# Power_Managemend_and_Connectors.net
KiCad netlist of a schematic drawn in Altium Designer
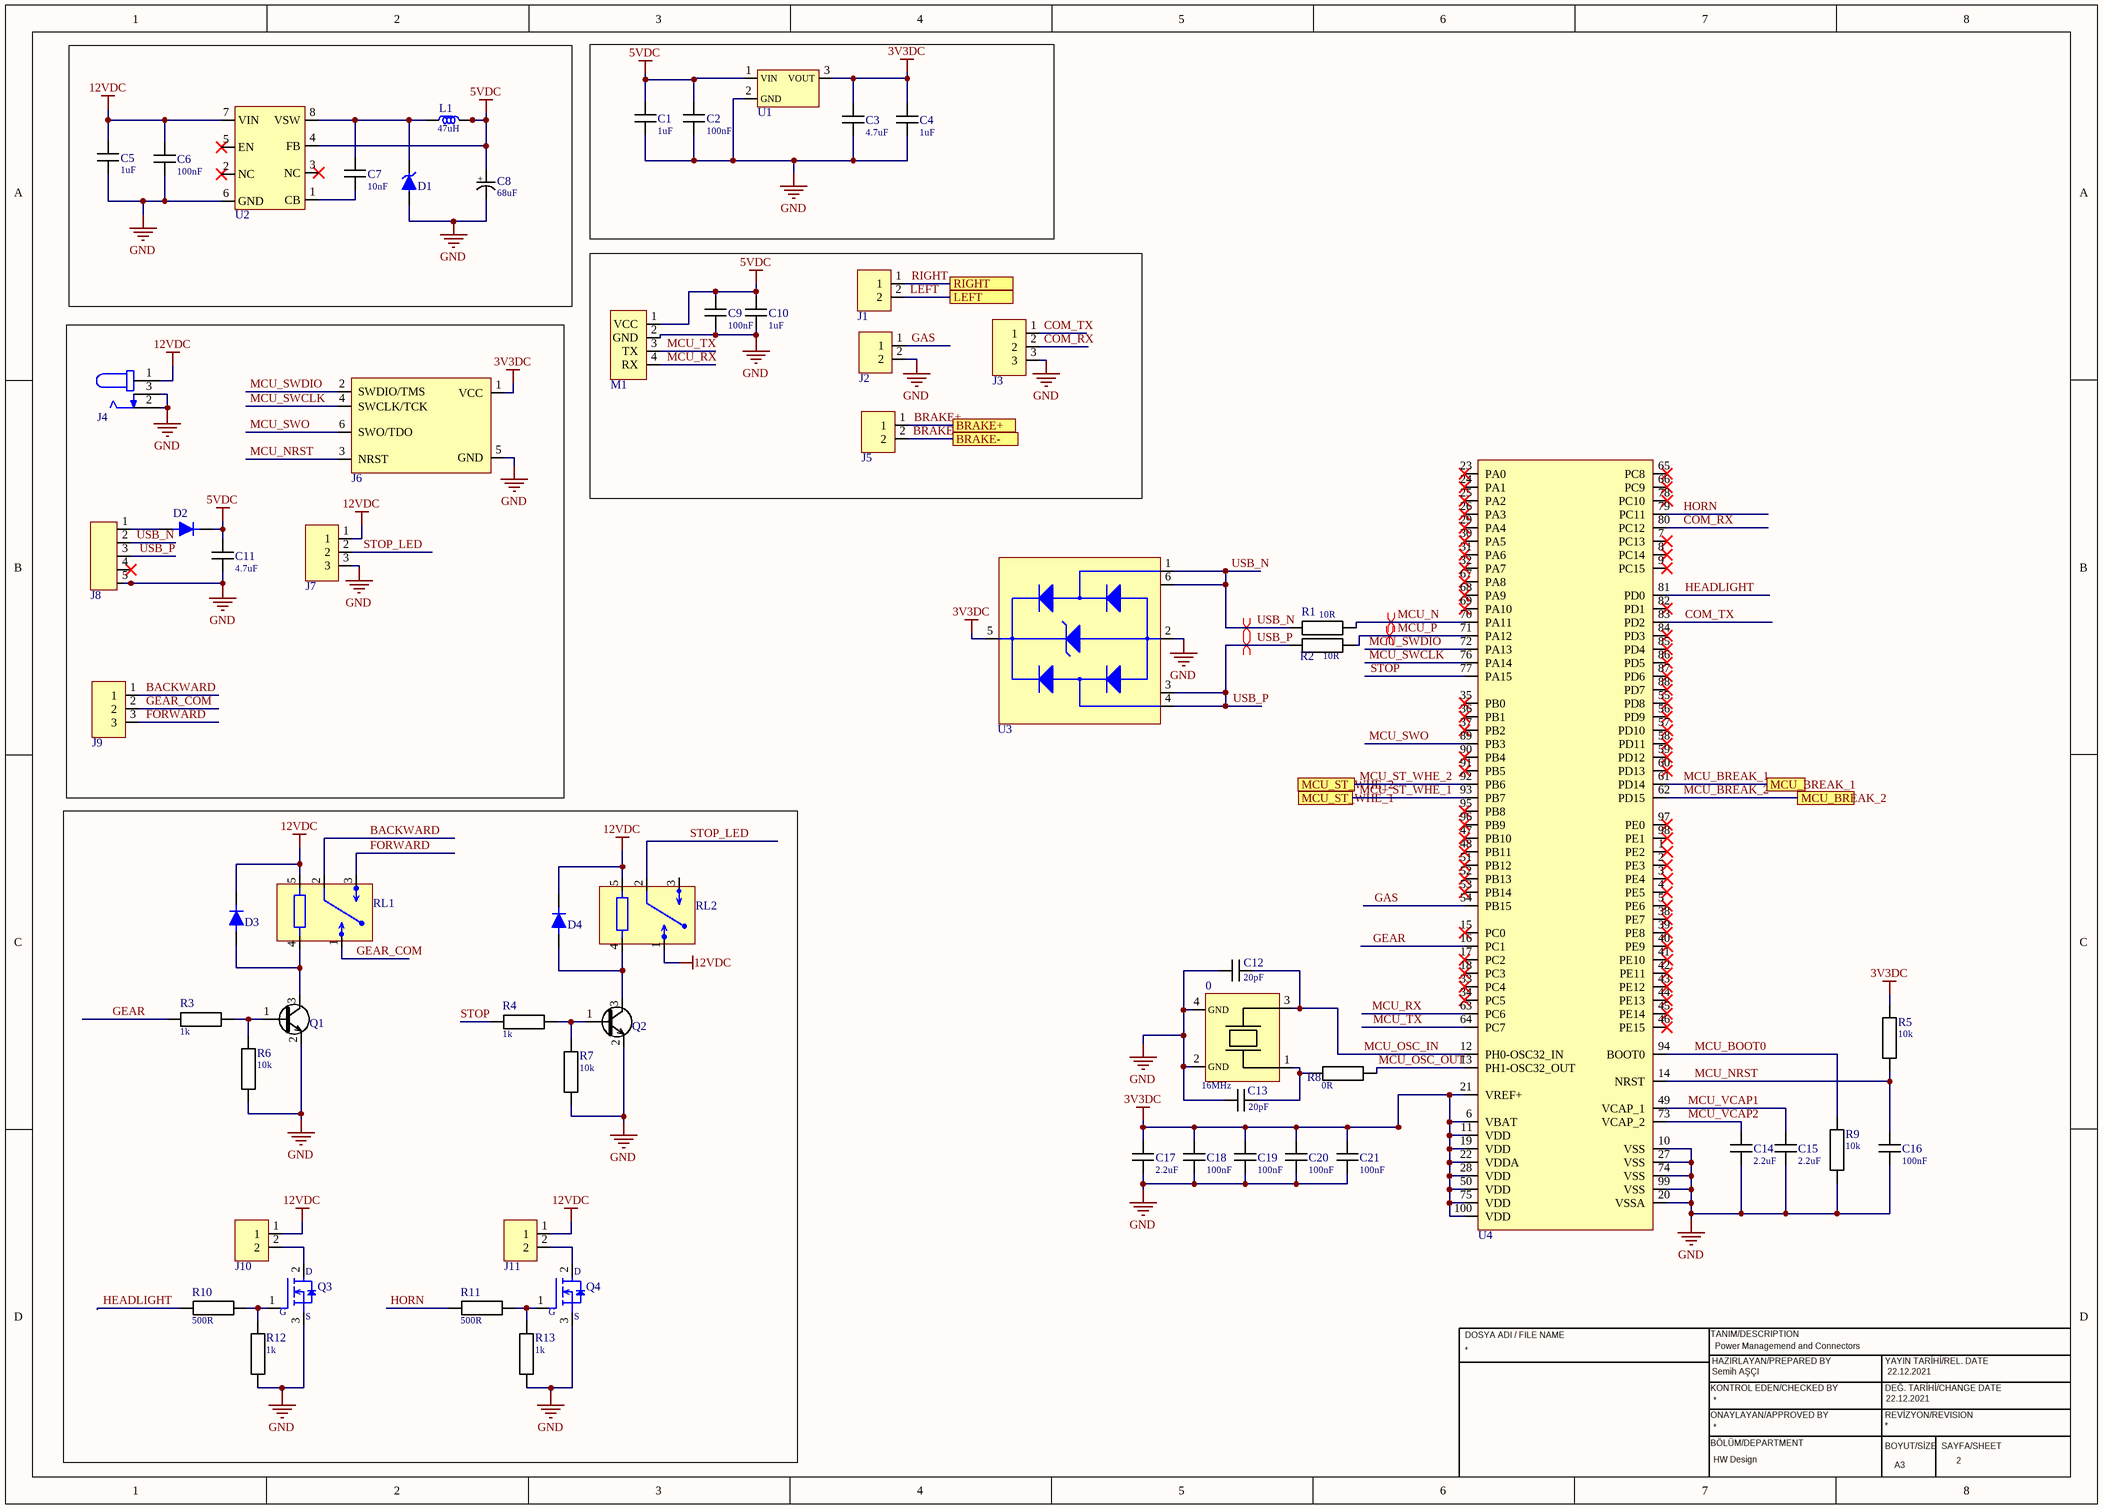
[diagram p0: Power Managemend and Connectors.SchDoc]

(export (version "E")
  (design (tool "Eeschema 10.0.6"))
  (components
    (comp (ref "0")
      (value "ECS-160-20-30B-TR")
      (footprint "ECS")
      (description "Crystal 16MHz ±30ppm (Tol) ±50ppm (Stability) 20pF FUND 50Ohm 4-Pin Mini-SMD T/R")
      (fields
        (field (name "MANUFACTURER") "ECS International")
        (field (name "TOLERANCE") "50ppm")
        (field (name "FREQUENCY") "16MHz")
        (field (name "DESIGNED BY") "Semih AŞÇI")
      )
      (libsource (lib "Integrated_Library1") (part "CRYSTAL 16 MHZ"))
    )
    (comp (ref "C1")
      (value "C0805C105M5RACTU")
      (footprint "CAP_0805")
      (description "Cap Ceramic 1uF %20 SMD 0805")
      (fields
        (field (name "MANUFACTURER") "KEMET")
        (field (name "TOLERANCE") "20%")
        (field (name "CAPACITANCE") "1uF")
        (field (name "DESIGNED BY") "Semih AŞÇI")
      )
      (libsource (lib "Integrated_Library1") (part "CAP 1uF 0805"))
    )
    (comp (ref "C2")
      (value "C0805C104K5RAC7800")
      (footprint "CAP_0805")
      (description "Cap Ceramic 100nF %10 SMD 0805")
      (fields
        (field (name "MANUFACTURER") "KEMET")
        (field (name "MANUFACTURER PART NUMBER") "C0805C104K5RACTU")
        (field (name "CAPACITANCE") "100nF")
        (field (name "DESIGNED BY") "Semih AŞÇI")
      )
      (libsource (lib "Integrated_Library1") (part "CAP 100nF 0805"))
    )
    (comp (ref "C3")
      (value "CL21A475KAQNNNE")
      (footprint "CAP_0805")
      (description "Cap Ceramic 4.7uF 25V X5R 10% SMD 0805 85C Embossed T/R")
      (fields
        (field (name "MANUFACTURER") "Samsung")
        (field (name "TOLERANCE") "10%")
        (field (name "CAPACITANCE") "4.7uF")
        (field (name "DESIGNED BY") "Semih AŞÇI")
      )
      (libsource (lib "Integrated_Library1") (part "CAP 4,7uF 0805"))
    )
    (comp (ref "C4")
      (value "C0805C105M5RACTU")
      (footprint "CAP_0805")
      (description "Cap Ceramic 1uF %20 SMD 0805")
      (fields
        (field (name "MANUFACTURER") "KEMET")
        (field (name "TOLERANCE") "20%")
        (field (name "CAPACITANCE") "1uF")
        (field (name "DESIGNED BY") "Semih AŞÇI")
      )
      (libsource (lib "Integrated_Library1") (part "CAP 1uF 0805"))
    )
    (comp (ref "C5")
      (value "C0805C105M5RACTU")
      (footprint "CAP_0805")
      (description "Cap Ceramic 1uF %20 SMD 0805")
      (fields
        (field (name "MANUFACTURER") "KEMET")
        (field (name "TOLERANCE") "20%")
        (field (name "CAPACITANCE") "1uF")
        (field (name "DESIGNED BY") "Semih AŞÇI")
      )
      (libsource (lib "Integrated_Library1") (part "CAP 1uF 0805"))
    )
    (comp (ref "C6")
      (value "C0805C104K5RAC7800")
      (footprint "CAP_0805")
      (description "Cap Ceramic 100nF %10 SMD 0805")
      (fields
        (field (name "MANUFACTURER") "KEMET")
        (field (name "MANUFACTURER PART NUMBER") "C0805C104K5RACTU")
        (field (name "CAPACITANCE") "100nF")
        (field (name "DESIGNED BY") "Semih AŞÇI")
      )
      (libsource (lib "Integrated_Library1") (part "CAP 100nF 0805"))
    )
    (comp (ref "C7")
      (value "0603B103K160CT")
      (footprint "CAP_0603")
      (description "Cap Ceramic 10nF %10 SMD 0603")
      (fields
        (field (name "MANUFACTURER") "Walsin Technologies")
        (field (name "TOLERANCE") "10%")
        (field (name "CAPACITANCE") "10nF")
        (field (name "DESIGNED BY") "Semih AŞÇI")
      )
      (libsource (lib "Integrated_Library1") (part "CAP 10nF 0603"))
    )
    (comp (ref "C8")
      (value "EEV686M035A9HAA")
      (footprint "CAP_ELEC_EEE-HA0J101WR")
      (description "Cap Aluminum Lytic 68uF 35V 20% (6.3 X 7.7mm) SMD 280mA 2000h 105C T/R")
      (fields
        (field (name "MANUFACTURER") "KEMET")
        (field (name "TOLERANCE") "20%")
        (field (name "CAPACITANCE") "68uF")
        (field (name "DESIGNED BY") "Semih AŞÇI")
      )
      (libsource (lib "Integrated_Library1") (part "CAP 68uF Polar SMD"))
    )
    (comp (ref "C9")
      (value "C0805C104K5RAC7800")
      (footprint "CAP_0805")
      (description "Cap Ceramic 100nF %10 SMD 0805")
      (fields
        (field (name "MANUFACTURER") "KEMET")
        (field (name "MANUFACTURER PART NUMBER") "C0805C104K5RACTU")
        (field (name "CAPACITANCE") "100nF")
        (field (name "DESIGNED BY") "Semih AŞÇI")
      )
      (libsource (lib "Integrated_Library1") (part "CAP 100nF 0805"))
    )
    (comp (ref "C10")
      (value "C0805C105M5RACTU")
      (footprint "CAP_0805")
      (description "Cap Ceramic 1uF %20 SMD 0805")
      (fields
        (field (name "MANUFACTURER") "KEMET")
        (field (name "TOLERANCE") "20%")
        (field (name "CAPACITANCE") "1uF")
        (field (name "DESIGNED BY") "Semih AŞÇI")
      )
      (libsource (lib "Integrated_Library1") (part "CAP 1uF 0805"))
    )
    (comp (ref "C11")
      (value "CL21A475KAQNNNE")
      (footprint "CAP_0805")
      (description "Cap Ceramic 4.7uF 25V X5R 10% SMD 0805 85C Embossed T/R")
      (fields
        (field (name "MANUFACTURER") "Samsung")
        (field (name "TOLERANCE") "10%")
        (field (name "CAPACITANCE") "4.7uF")
        (field (name "DESIGNED BY") "Semih AŞÇI")
      )
      (libsource (lib "Integrated_Library1") (part "CAP 4,7uF 0805"))
    )
    (comp (ref "C12")
      (value "C0603C200F5GAC7867")
      (footprint "CAP_0603")
      (description "Cap Ceramic 20pF SMD 0603")
      (fields
        (field (name "MANUFACTURER") "KEMET")
        (field (name "CAPACITANCE") "20pF")
        (field (name "DESIGNED BY") "Semih AŞÇI")
      )
      (libsource (lib "Integrated_Library1") (part "CAP 20pF 0603"))
    )
    (comp (ref "C13")
      (value "C0603C200F5GAC7867")
      (footprint "CAP_0603")
      (description "Cap Ceramic 20pF SMD 0603")
      (fields
        (field (name "MANUFACTURER") "KEMET")
        (field (name "CAPACITANCE") "20pF")
        (field (name "DESIGNED BY") "Semih AŞÇI")
      )
      (libsource (lib "Integrated_Library1") (part "CAP 20pF 0603"))
    )
    (comp (ref "C14")
      (value "C1206C225K5RACAUTO")
      (footprint "CAP_1206")
      (description "Cap Ceramic 2.2uF %10 SMD 1206")
      (fields
        (field (name "MANUFACTURER") "KEMET")
        (field (name "TOLERANCE") "10%")
        (field (name "CAPACITANCE") "2.2uF")
        (field (name "DESIGNED BY") "Semih AŞÇI")
      )
      (libsource (lib "Integrated_Library1") (part "CAP 2.2uF 1206"))
    )
    (comp (ref "C15")
      (value "C1206C225K5RACAUTO")
      (footprint "CAP_1206")
      (description "Cap Ceramic 2.2uF %10 SMD 1206")
      (fields
        (field (name "MANUFACTURER") "KEMET")
        (field (name "TOLERANCE") "10%")
        (field (name "CAPACITANCE") "2.2uF")
        (field (name "DESIGNED BY") "Semih AŞÇI")
      )
      (libsource (lib "Integrated_Library1") (part "CAP 2.2uF 1206"))
    )
    (comp (ref "C16")
      (value "C0805C104K5RAC7800")
      (footprint "CAP_0805")
      (description "Cap Ceramic 100nF %10 SMD 0805")
      (fields
        (field (name "MANUFACTURER") "KEMET")
        (field (name "MANUFACTURER PART NUMBER") "C0805C104K5RACTU")
        (field (name "CAPACITANCE") "100nF")
        (field (name "DESIGNED BY") "Semih AŞÇI")
      )
      (libsource (lib "Integrated_Library1") (part "CAP 100nF 0805"))
    )
    (comp (ref "C17")
      (value "C1206C225K5RACAUTO")
      (footprint "CAP_1206")
      (description "Cap Ceramic 2.2uF %10 SMD 1206")
      (fields
        (field (name "MANUFACTURER") "KEMET")
        (field (name "TOLERANCE") "10%")
        (field (name "CAPACITANCE") "2.2uF")
        (field (name "DESIGNED BY") "Semih AŞÇI")
      )
      (libsource (lib "Integrated_Library1") (part "CAP 2.2uF 1206"))
    )
    (comp (ref "C18")
      (value "C0805C104K5RAC7800")
      (footprint "CAP_0805")
      (description "Cap Ceramic 100nF %10 SMD 0805")
      (fields
        (field (name "MANUFACTURER") "KEMET")
        (field (name "MANUFACTURER PART NUMBER") "C0805C104K5RACTU")
        (field (name "CAPACITANCE") "100nF")
        (field (name "DESIGNED BY") "Semih AŞÇI")
      )
      (libsource (lib "Integrated_Library1") (part "CAP 100nF 0805"))
    )
    (comp (ref "C19")
      (value "C0805C104K5RAC7800")
      (footprint "CAP_0805")
      (description "Cap Ceramic 100nF %10 SMD 0805")
      (fields
        (field (name "MANUFACTURER") "KEMET")
        (field (name "MANUFACTURER PART NUMBER") "C0805C104K5RACTU")
        (field (name "CAPACITANCE") "100nF")
        (field (name "DESIGNED BY") "Semih AŞÇI")
      )
      (libsource (lib "Integrated_Library1") (part "CAP 100nF 0805"))
    )
    (comp (ref "C20")
      (value "C0805C104K5RAC7800")
      (footprint "CAP_0805")
      (description "Cap Ceramic 100nF %10 SMD 0805")
      (fields
        (field (name "MANUFACTURER") "KEMET")
        (field (name "MANUFACTURER PART NUMBER") "C0805C104K5RACTU")
        (field (name "CAPACITANCE") "100nF")
        (field (name "DESIGNED BY") "Semih AŞÇI")
      )
      (libsource (lib "Integrated_Library1") (part "CAP 100nF 0805"))
    )
    (comp (ref "C21")
      (value "C0805C104K5RAC7800")
      (footprint "CAP_0805")
      (description "Cap Ceramic 100nF %10 SMD 0805")
      (fields
        (field (name "MANUFACTURER") "KEMET")
        (field (name "MANUFACTURER PART NUMBER") "C0805C104K5RACTU")
        (field (name "CAPACITANCE") "100nF")
        (field (name "DESIGNED BY") "Semih AŞÇI")
      )
      (libsource (lib "Integrated_Library1") (part "CAP 100nF 0805"))
    )
    (comp (ref "D1")
      (value "1SMB5919BT3G")
      (footprint "SMB")
      (description "Diode, Zener, Vr 5.6V, If 200mA, Pkg SMB, Vf 1.5V, Tj +150degc, Pd 3W, Ir 66.9mA")
      (fields
        (field (name "MANUFACTURER") "ON Semiconductor")
        (field (name "TOLERANCE") "5%")
        (field (name "DESIGNED BY") "Semih AŞÇI")
      )
      (libsource (lib "Integrated_Library1") (part "1SMB5919BT3G"))
    )
    (comp (ref "D2")
      (value "1N4148WS")
      (footprint "SOD323F")
      (description "Diode Small Signal Switching 100V 0.15A Automotive 2-Pin SOD-323F T/R")
      (fields
        (field (name "MANUFACTURER") "ON Semiconductor / Fairchild")
        (field (name "DESIGNED BY") "Semih AŞÇI")
      )
      (libsource (lib "Integrated_Library1") (part "1N4148SW"))
    )
    (comp (ref "D3")
      (value "1N4148WS")
      (footprint "SOD323F")
      (description "Diode Small Signal Switching 100V 0.15A Automotive 2-Pin SOD-323F T/R")
      (fields
        (field (name "MANUFACTURER") "ON Semiconductor / Fairchild")
        (field (name "DESIGNED BY") "Semih AŞÇI")
      )
      (libsource (lib "Integrated_Library1") (part "1N4148SW"))
    )
    (comp (ref "D4")
      (value "1N4148WS")
      (footprint "SOD323F")
      (description "Diode Small Signal Switching 100V 0.15A Automotive 2-Pin SOD-323F T/R")
      (fields
        (field (name "MANUFACTURER") "ON Semiconductor / Fairchild")
        (field (name "DESIGNED BY") "Semih AŞÇI")
      )
      (libsource (lib "Integrated_Library1") (part "1N4148SW"))
    )
    (comp (ref "J1")
      (value "B2P-VH-BK")
      (footprint "2x1_HEADER")
      (fields (field (name "DESIGNED BY") "Semih AŞÇI"))
      (libsource (lib "Integrated_Library1") (part "2x1 Header"))
    )
    (comp (ref "J2")
      (value "B2P-VH-BK")
      (footprint "2x1_HEADER")
      (fields (field (name "DESIGNED BY") "Semih AŞÇI"))
      (libsource (lib "Integrated_Library1") (part "2x1 Header"))
    )
    (comp (ref "J3")
      (value "B3P-VH-BK")
      (footprint "3x1_HEADER")
      (fields (field (name "DESIGNED BY") "Semih AŞÇI"))
      (libsource (lib "Integrated_Library1") (part "3x1 Header"))
    )
    (comp (ref "J4")
      (value "PJ-037AH-SMT-TR")
      (footprint "POWER_JACK")
      (description "2.0 x 6.3 mm, 5.0 A, Horizontal, Surface Mount (SMT), Dc Power Jack Connector")
      (fields (field (name "MANUFACTURER") "CUI") (field (name "DESIGNED BY") "Semih AŞÇI"))
      (libsource (lib "Integrated_Library1") (part "PJ-037AH-SMT-TR"))
    )
    (comp (ref "J5")
      (value "B2P-VH-BK")
      (footprint "2x1_HEADER")
      (fields (field (name "DESIGNED BY") "Semih AŞÇI"))
      (libsource (lib "Integrated_Library1") (part "2x1 Header"))
    )
    (comp (ref "J6")
      (value "TC2030-STK")
      (footprint "TC2030")
      (description "TC2030-MCP/TC2030-MCP-NL Cable Assembly Other Development Tool")
      (fields (field (name "MANUFACTURER") "Microchip") (field (name "DESIGNED BY") "Semih AŞÇI"))
      (libsource (lib "Integrated_Library1") (part "TC2030-STK"))
    )
    (comp (ref "J7")
      (value "B3P-VH-BK")
      (footprint "3x1_HEADER")
      (fields (field (name "DESIGNED BY") "Semih AŞÇI"))
      (libsource (lib "Integrated_Library1") (part "3x1 Header"))
    )
    (comp (ref "J8")
      (value "10118192-0001LF")
      (footprint "MICRO_B_USB")
      (description "FCI Right Angle Surface Mount Mount Female USB Connector; 100 V ac; 1.8A")
      (fields (field (name "MANUFACTURER") "Amphenol ICC / FCI"))
      (libsource (lib "Integrated_Library1") (part "Micro B USB Connector"))
    )
    (comp (ref "J9")
      (value "B3P-VH-BK")
      (footprint "3x1_HEADER")
      (fields (field (name "DESIGNED BY") "Semih AŞÇI"))
      (libsource (lib "Integrated_Library1") (part "3x1 Header"))
    )
    (comp (ref "J10")
      (value "B2P-VH-BK")
      (footprint "2x1_HEADER")
      (fields (field (name "DESIGNED BY") "Semih AŞÇI"))
      (libsource (lib "Integrated_Library1") (part "2x1 Header"))
    )
    (comp (ref "J11")
      (value "B2P-VH-BK")
      (footprint "2x1_HEADER")
      (fields (field (name "DESIGNED BY") "Semih AŞÇI"))
      (libsource (lib "Integrated_Library1") (part "2x1 Header"))
    )
    (comp (ref "L1")
      (value "78438335470")
      (footprint "IND_1212")
      (description "Fixed Ind 47UH 390MA 2.3 Ohm SMD")
      (fields
        (field (name "MANUFACTURER") "Wurth Electronics")
        (field (name "TOLERANCE") "30%")
        (field (name "INDUCTANCE") "47uH")
        (field (name "DESIGNED BY") "Semih AŞÇI")
      )
      (libsource (lib "Integrated_Library1") (part "IND 47uH"))
    )
    (comp (ref "M1")
      (value "HC06")
      (footprint "HC06")
      (fields (field (name "DESIGNED BY") "Semih AŞÇI"))
      (libsource (lib "Integrated_Library1") (part "HC06"))
    )
    (comp (ref "Q1")
      (value "MMBT3904-7-F")
      (footprint "SOT23-F")
      (description "Transistor General Purpose BJT NPN 40 Volt 0.2A Automotive 3-Pin SOT-23")
      (fields (field (name "MANUFACTURER") "Diodes Zetex") (field (name "DESIGNED BY") "Semih AŞÇI"))
      (libsource (lib "Integrated_Library1") (part "MMBT3904-7-F"))
    )
    (comp (ref "Q2")
      (value "MMBT3904-7-F")
      (footprint "SOT23-F")
      (description "Transistor General Purpose BJT NPN 40 Volt 0.2A Automotive 3-Pin SOT-23")
      (fields (field (name "MANUFACTURER") "Diodes Zetex") (field (name "DESIGNED BY") "Semih AŞÇI"))
      (libsource (lib "Integrated_Library1") (part "MMBT3904-7-F"))
    )
    (comp (ref "Q3")
      (value "IRF3710STRLPBF")
      (footprint "TO-263-3")
      (description "Single N-Channel 100 V 23 mOhm 130nC HEXFET® Power Mosfet - D2PAK")
      (fields
        (field (name "MANUFACTURER") "International Rectifier")
        (field (name "DESIGNED BY") "Semih AŞÇI")
      )
      (libsource (lib "Integrated_Library1") (part "IRF3710STRLPBF"))
    )
    (comp (ref "Q4")
      (value "IRF3710STRLPBF")
      (footprint "TO-263-3")
      (description "Single N-Channel 100 V 23 mOhm 130nC HEXFET® Power Mosfet - D2PAK")
      (fields
        (field (name "MANUFACTURER") "International Rectifier")
        (field (name "DESIGNED BY") "Semih AŞÇI")
      )
      (libsource (lib "Integrated_Library1") (part "IRF3710STRLPBF"))
    )
    (comp (ref "R1")
      (value "RC0805FR-0710RL")
      (footprint "CAP_0805")
      (description "Res 10 Ohm %1 SMD 0805")
      (fields
        (field (name "MANUFACTURER") "Yageo")
        (field (name "TOLERANCE") "1%")
        (field (name "RESISTANCE") "10R")
        (field (name "DESIGNED BY") "Semih AŞÇI")
      )
      (libsource (lib "Integrated_Library1") (part "RES 10 OHM 0805"))
    )
    (comp (ref "R2")
      (value "RC0805FR-0710RL")
      (footprint "CAP_0805")
      (description "Res 10 Ohm %1 SMD 0805")
      (fields
        (field (name "MANUFACTURER") "Yageo")
        (field (name "TOLERANCE") "1%")
        (field (name "RESISTANCE") "10R")
        (field (name "DESIGNED BY") "Semih AŞÇI")
      )
      (libsource (lib "Integrated_Library1") (part "RES 10 OHM 0805"))
    )
    (comp (ref "R3")
      (value "RC0805FR-071KL")
      (footprint "RES_0805")
      (description "Res 1K Ohm %1 SMD 0805")
      (fields
        (field (name "MANUFACTURER") "Yageo")
        (field (name "TOLERANCE") "1%")
        (field (name "RESISTANCE") "1k")
        (field (name "DESIGNED BY") "Semih AŞÇI")
      )
      (libsource (lib "Integrated_Library1") (part "RES 1k OHM 0805"))
    )
    (comp (ref "R4")
      (value "RC0805FR-071KL")
      (footprint "RES_0805")
      (description "Res 1K Ohm %1 SMD 0805")
      (fields
        (field (name "MANUFACTURER") "Yageo")
        (field (name "TOLERANCE") "1%")
        (field (name "RESISTANCE") "1k")
        (field (name "DESIGNED BY") "Semih AŞÇI")
      )
      (libsource (lib "Integrated_Library1") (part "RES 1k OHM 0805"))
    )
    (comp (ref "R5")
      (value "RC0603FR-0710KL")
      (footprint "RES_0603")
      (description "Res General Purpose Thick Film 0603 10K Ohm 1% 1/10W ±100ppm/°C Molded SMD Paper T/R")
      (fields
        (field (name "MANUFACTURER") "Yageo")
        (field (name "TOLERANCE") "1%")
        (field (name "RESISTANCE") "10k")
        (field (name "DESIGNED BY") "Semih AŞÇI")
      )
      (libsource (lib "Integrated_Library1") (part "RES 10k OHM 0603"))
    )
    (comp (ref "R6")
      (value "RC0603FR-0710KL")
      (footprint "RES_0603")
      (description "Res General Purpose Thick Film 0603 10K Ohm 1% 1/10W ±100ppm/°C Molded SMD Paper T/R")
      (fields
        (field (name "MANUFACTURER") "Yageo")
        (field (name "TOLERANCE") "1%")
        (field (name "RESISTANCE") "10k")
        (field (name "DESIGNED BY") "Semih AŞÇI")
      )
      (libsource (lib "Integrated_Library1") (part "RES 10k OHM 0603"))
    )
    (comp (ref "R7")
      (value "RC0603FR-0710KL")
      (footprint "RES_0603")
      (description "Res General Purpose Thick Film 0603 10K Ohm 1% 1/10W ±100ppm/°C Molded SMD Paper T/R")
      (fields
        (field (name "MANUFACTURER") "Yageo")
        (field (name "TOLERANCE") "1%")
        (field (name "RESISTANCE") "10k")
        (field (name "DESIGNED BY") "Semih AŞÇI")
      )
      (libsource (lib "Integrated_Library1") (part "RES 10k OHM 0603"))
    )
    (comp (ref "R8")
      (value "RC0603JR-070RL")
      (footprint "RES_0603")
      (description "RES SMD 0 OHM JUMPER 1/10W 0603")
      (fields
        (field (name "MANUFACTURER") "Yageo")
        (field (name "TOLERANCE") "1%")
        (field (name "RESISTANCE") "0R")
        (field (name "DESIGNED BY") "Semih AŞÇI")
      )
      (libsource (lib "Integrated_Library1") (part "RES 0 OHM 0603"))
    )
    (comp (ref "R9")
      (value "RC0603FR-0710KL")
      (footprint "RES_0603")
      (description "Res General Purpose Thick Film 0603 10K Ohm 1% 1/10W ±100ppm/°C Molded SMD Paper T/R")
      (fields
        (field (name "MANUFACTURER") "Yageo")
        (field (name "TOLERANCE") "1%")
        (field (name "RESISTANCE") "10k")
        (field (name "DESIGNED BY") "Semih AŞÇI")
      )
      (libsource (lib "Integrated_Library1") (part "RES 10k OHM 0603"))
    )
    (comp (ref "R10")
      (value "PLT0805Z5000AST5")
      (footprint "RES_0805")
      (description "Res 500 Ohm %0.05  SMD 0805")
      (fields
        (field (name "MANUFACTURER") "Vishay Dale Thin Film")
        (field (name "RESISTANCE") "500R")
        (field (name "DESIGNED BY") "Semih AŞÇI")
      )
      (libsource (lib "Integrated_Library1") (part "RES 500 OHM 0805"))
    )
    (comp (ref "R11")
      (value "PLT0805Z5000AST5")
      (footprint "RES_0805")
      (description "Res 500 Ohm %0.05  SMD 0805")
      (fields
        (field (name "MANUFACTURER") "Vishay Dale Thin Film")
        (field (name "RESISTANCE") "500R")
        (field (name "DESIGNED BY") "Semih AŞÇI")
      )
      (libsource (lib "Integrated_Library1") (part "RES 500 OHM 0805"))
    )
    (comp (ref "R12")
      (value "RC0805FR-071KL")
      (footprint "RES_0805")
      (description "Res 1K Ohm %1 SMD 0805")
      (fields
        (field (name "MANUFACTURER") "Yageo")
        (field (name "TOLERANCE") "1%")
        (field (name "RESISTANCE") "1k")
        (field (name "DESIGNED BY") "Semih AŞÇI")
      )
      (libsource (lib "Integrated_Library1") (part "RES 1k OHM 0805"))
    )
    (comp (ref "R13")
      (value "RC0805FR-071KL")
      (footprint "RES_0805")
      (description "Res 1K Ohm %1 SMD 0805")
      (fields
        (field (name "MANUFACTURER") "Yageo")
        (field (name "TOLERANCE") "1%")
        (field (name "RESISTANCE") "1k")
        (field (name "DESIGNED BY") "Semih AŞÇI")
      )
      (libsource (lib "Integrated_Library1") (part "RES 1k OHM 0805"))
    )
    (comp (ref "RL1")
      (value "ALQ112")
      (footprint "ALQ112")
      (description "PANASONIC - ALQ112 - POWER RELAY, SPDT, 12VDC, 10A, THD")
      (fields (field (name "MANUFACTURER") "Panasonic") (field (name "DESIGNED BY") "Semih AŞÇI"))
      (libsource (lib "Integrated_Library1") (part "ALQ112"))
    )
    (comp (ref "RL2")
      (value "ALQ112")
      (footprint "ALQ112")
      (description "PANASONIC - ALQ112 - POWER RELAY, SPDT, 12VDC, 10A, THD")
      (fields (field (name "MANUFACTURER") "Panasonic") (field (name "DESIGNED BY") "Semih AŞÇI"))
      (libsource (lib "Integrated_Library1") (part "ALQ112"))
    )
    (comp (ref "U1")
      (value "AP7361-33E-13")
      (footprint "SOT223")
      (description "AP7361 Series 3.3 V 1 A Low SMT Dropout Fixed-Mode Regulator - SOT-223")
      (fields (field (name "MANUFACTURER") "Diodes") (field (name "DESIGNED BY") "Semih AŞÇI"))
      (libsource (lib "Integrated_Library1") (part "AP7361-33E-13"))
    )
    (comp (ref "U2")
      (value "LM2675MX-12/NOPB")
      (footprint "SOIC8")
      (description "SIMPLE SWITCHER® 6.5V to 40V, 1A Low Component Count Step-Down Regulator 8-SOIC -40 to 125")
      (fields
        (field (name "MANUFACTURER") "TI National Semiconductor")
        (field (name "DESIGNED BY") "Semih AŞÇI")
      )
      (libsource (lib "Integrated_Library1") (part "LM2675MX-12/NOPB"))
    )
    (comp (ref "U3")
      (value "USBLC6_2SC6")
      (footprint "SOT23-6L")
      (description "USBLC6 Series 2 Line 6 V Uni / Bi-Directional ESD Protection - SOT-23-6")
      (fields
        (field (name "MANUFACTURER") "STMicroelectronics")
        (field (name "MANUFACTURER PART NUMBER") "USBLC6-2SC6")
        (field (name "DESIGNED BY") "Semih AŞÇI")
      )
      (libsource (lib "Integrated_Library1") (part "USB PROTECTION"))
    )
    (comp (ref "U4")
      (value "497-11605-ND")
      (footprint "100-LQFP")
      (description "MCU 32-bit STM32F ARM Cortex M4F RISC 1024KB Flash 2.5V/3.3V 100-Pin LQFP Tray")
      (fields
        (field (name "MANUFACTURER") "STMicroelectronics")
        (field (name "MANUFACTURER PART NUMBER") "STM32F407VGT6")
        (field (name "DESIGNED BY") "Semih AŞÇI")
      )
      (libsource (lib "Integrated_Library1") (part "STM32F407VGT6"))
    )
  )
  (nets
    (net (code "1") (name "/BACKWARD") (class "Default")
      (node (ref "J9") (pin "1") (pinfunction "1_1") (pintype "passive"))
      (node (ref "RL1") (pin "2") (pinfunction "2_2") (pintype "passive"))
    )
    (net (code "2") (name "/BRAKE+") (class "Default")
      (node (ref "J5") (pin "1") (pinfunction "1_1") (pintype "passive"))
    )
    (net (code "3") (name "/BRAKE-") (class "Default")
      (node (ref "J5") (pin "2") (pinfunction "2_2") (pintype "passive"))
    )
    (net (code "4") (name "/COM_RX") (class "Default")
      (node (ref "J3") (pin "2") (pinfunction "2_2") (pintype "passive"))
      (node (ref "U4") (pin "80") (pinfunction "PC12_80") (pintype "passive"))
    )
    (net (code "5") (name "/COM_TX") (class "Default")
      (node (ref "J3") (pin "1") (pinfunction "1_1") (pintype "passive"))
      (node (ref "U4") (pin "83") (pinfunction "PD2_83") (pintype "passive"))
    )
    (net (code "6") (name "/FORWARD") (class "Default")
      (node (ref "J9") (pin "3") (pinfunction "3_3") (pintype "passive"))
      (node (ref "RL1") (pin "3") (pinfunction "3_3") (pintype "passive"))
    )
    (net (code "7") (name "/GAS") (class "Default")
      (node (ref "J2") (pin "1") (pinfunction "1_1") (pintype "passive"))
      (node (ref "U4") (pin "54") (pinfunction "PB15_54") (pintype "passive"))
    )
    (net (code "8") (name "/GEAR") (class "Default")
      (node (ref "R3") (pin "1") (pinfunction "1_1") (pintype "passive"))
      (node (ref "U4") (pin "16") (pinfunction "PC1_16") (pintype "passive"))
    )
    (net (code "9") (name "/GEAR_COM") (class "Default")
      (node (ref "J9") (pin "2") (pinfunction "2_2") (pintype "passive"))
      (node (ref "RL1") (pin "1") (pinfunction "1_1") (pintype "passive"))
    )
    (net (code "10") (name "/HEADLIGHT") (class "Default")
      (node (ref "R10") (pin "1") (pinfunction "1_1") (pintype "passive"))
      (node (ref "U4") (pin "81") (pinfunction "PD0_81") (pintype "passive"))
    )
    (net (code "11") (name "/HORN") (class "Default")
      (node (ref "R11") (pin "1") (pinfunction "1_1") (pintype "passive"))
      (node (ref "U4") (pin "79") (pinfunction "PC11_79") (pintype "passive"))
    )
    (net (code "12") (name "/LEFT") (class "Default")
      (node (ref "J1") (pin "2") (pinfunction "2_2") (pintype "passive"))
    )
    (net (code "13") (name "/MCU_BOOT0") (class "Default")
      (node (ref "R9") (pin "2") (pinfunction "2_2") (pintype "passive"))
      (node (ref "U4") (pin "94") (pinfunction "BOOT0_94") (pintype "passive"))
    )
    (net (code "14") (name "/MCU_BREAK_1") (class "Default")
      (node (ref "U4") (pin "61") (pinfunction "PD14_61") (pintype "passive"))
    )
    (net (code "15") (name "/MCU_BREAK_2") (class "Default")
      (node (ref "U4") (pin "62") (pinfunction "PD15_62") (pintype "passive"))
    )
    (net (code "16") (name "/MCU_N") (class "Default")
      (node (ref "R1") (pin "2") (pinfunction "2_2") (pintype "passive"))
      (node (ref "U4") (pin "70") (pinfunction "PA11_70") (pintype "passive"))
    )
    (net (code "17") (name "/MCU_NRST") (class "Default")
      (node (ref "C16") (pin "1") (pinfunction "1_1") (pintype "passive"))
      (node (ref "J6") (pin "3") (pinfunction "NRST_3") (pintype "passive"))
      (node (ref "R5") (pin "1") (pinfunction "1_1") (pintype "passive"))
      (node (ref "U4") (pin "14") (pinfunction "NRST_14") (pintype "passive"))
    )
    (net (code "18") (name "/MCU_OSC_IN") (class "Default")
      (node (ref "0") (pin "3") (pinfunction "3_3") (pintype "passive"))
      (node (ref "C12") (pin "2") (pinfunction "2_2") (pintype "passive"))
      (node (ref "U4") (pin "12") (pinfunction "PH0-OSC32_IN_12") (pintype "passive"))
    )
    (net (code "19") (name "/MCU_OSC_OUT") (class "Default")
      (node (ref "R8") (pin "2") (pinfunction "2_2") (pintype "passive"))
      (node (ref "U4") (pin "13") (pinfunction "PH1-OSC32_OUT_13") (pintype "passive"))
    )
    (net (code "20") (name "/MCU_P") (class "Default")
      (node (ref "R2") (pin "2") (pinfunction "2_2") (pintype "passive"))
      (node (ref "U4") (pin "71") (pinfunction "PA12_71") (pintype "passive"))
    )
    (net (code "21") (name "/MCU_RX") (class "Default")
      (node (ref "M1") (pin "4") (pinfunction "RX_4") (pintype "passive"))
      (node (ref "U4") (pin "63") (pinfunction "PC6_63") (pintype "passive"))
    )
    (net (code "22") (name "/MCU_ST_WHE_1") (class "Default")
      (node (ref "U4") (pin "93") (pinfunction "PB7_93") (pintype "passive"))
    )
    (net (code "23") (name "/MCU_ST_WHE_2") (class "Default")
      (node (ref "U4") (pin "92") (pinfunction "PB6_92") (pintype "passive"))
    )
    (net (code "24") (name "/MCU_SWCLK") (class "Default")
      (node (ref "J6") (pin "4") (pinfunction "SWCLK/TCK_4") (pintype "passive"))
      (node (ref "U4") (pin "76") (pinfunction "PA14_76") (pintype "passive"))
    )
    (net (code "25") (name "/MCU_SWDIO") (class "Default")
      (node (ref "J6") (pin "2") (pinfunction "SWDIO/TMS_2") (pintype "passive"))
      (node (ref "U4") (pin "72") (pinfunction "PA13_72") (pintype "passive"))
    )
    (net (code "26") (name "/MCU_SWO") (class "Default")
      (node (ref "J6") (pin "6") (pinfunction "SWO/TDO_6") (pintype "passive"))
      (node (ref "U4") (pin "89") (pinfunction "PB3_89") (pintype "passive"))
    )
    (net (code "27") (name "/MCU_TX") (class "Default")
      (node (ref "M1") (pin "3") (pinfunction "TX_3") (pintype "passive"))
      (node (ref "U4") (pin "64") (pinfunction "PC7_64") (pintype "passive"))
    )
    (net (code "28") (name "/MCU_VCAP1") (class "Default")
      (node (ref "C15") (pin "2") (pinfunction "2_2") (pintype "passive"))
      (node (ref "U4") (pin "49") (pinfunction "VCAP_1_49") (pintype "passive"))
    )
    (net (code "29") (name "/MCU_VCAP2") (class "Default")
      (node (ref "C14") (pin "2") (pinfunction "2_2") (pintype "passive"))
      (node (ref "U4") (pin "73") (pinfunction "VCAP_2_73") (pintype "passive"))
    )
    (net (code "30") (name "/RIGHT") (class "Default")
      (node (ref "J1") (pin "1") (pinfunction "1_1") (pintype "passive"))
    )
    (net (code "31") (name "/STOP") (class "Default")
      (node (ref "R4") (pin "1") (pinfunction "1_1") (pintype "passive"))
      (node (ref "U4") (pin "77") (pinfunction "PA15_77") (pintype "passive"))
    )
    (net (code "32") (name "/STOP_LED") (class "Default")
      (node (ref "J7") (pin "2") (pinfunction "2_2") (pintype "passive"))
      (node (ref "RL2") (pin "2") (pinfunction "2_2") (pintype "passive"))
    )
    (net (code "33") (name "/USB_N") (class "Default")
      (node (ref "J8") (pin "2") (pinfunction "Rx_2") (pintype "passive"))
      (node (ref "R1") (pin "1") (pinfunction "1_1") (pintype "passive"))
      (node (ref "U3") (pin "1") (pinfunction "I/O1_1") (pintype "bidirectional"))
      (node (ref "U3") (pin "6") (pinfunction "I/O1_6") (pintype "bidirectional"))
    )
    (net (code "34") (name "/USB_P") (class "Default")
      (node (ref "J8") (pin "3") (pinfunction "Tx_3") (pintype "passive"))
      (node (ref "R2") (pin "1") (pinfunction "1_1") (pintype "passive"))
      (node (ref "U3") (pin "3") (pinfunction "I/O2_3") (pintype "bidirectional"))
      (node (ref "U3") (pin "4") (pinfunction "I/O2_4") (pintype "bidirectional"))
    )
    (net (code "35") (name "3V3DC") (class "Default")
      (node (ref "C17") (pin "2") (pinfunction "2_2") (pintype "passive"))
      (node (ref "C18") (pin "1") (pinfunction "1_1") (pintype "passive"))
      (node (ref "C19") (pin "1") (pinfunction "1_1") (pintype "passive"))
      (node (ref "C20") (pin "1") (pinfunction "1_1") (pintype "passive"))
      (node (ref "C21") (pin "1") (pinfunction "1_1") (pintype "passive"))
      (node (ref "C3") (pin "2") (pinfunction "2_2") (pintype "passive"))
      (node (ref "C4") (pin "2") (pinfunction "2_2") (pintype "passive"))
      (node (ref "J6") (pin "1") (pinfunction "VCC_1") (pintype "passive"))
      (node (ref "R5") (pin "2") (pinfunction "2_2") (pintype "passive"))
      (node (ref "U1") (pin "3") (pinfunction "VOUT_3") (pintype "passive"))
      (node (ref "U3") (pin "5") (pinfunction "VBUS_5") (pintype "power_in"))
      (node (ref "U4") (pin "100") (pinfunction "VDD_100") (pintype "passive"))
      (node (ref "U4") (pin "11") (pinfunction "VDD_11") (pintype "passive"))
      (node (ref "U4") (pin "19") (pinfunction "VDD_19") (pintype "passive"))
      (node (ref "U4") (pin "21") (pinfunction "VREF+_21") (pintype "passive"))
      (node (ref "U4") (pin "22") (pinfunction "VDDA_22") (pintype "passive"))
      (node (ref "U4") (pin "28") (pinfunction "VDD_28") (pintype "passive"))
      (node (ref "U4") (pin "50") (pinfunction "VDD_50") (pintype "passive"))
      (node (ref "U4") (pin "6") (pinfunction "VBAT_6") (pintype "passive"))
      (node (ref "U4") (pin "75") (pinfunction "VDD_75") (pintype "passive"))
    )
    (net (code "36") (name "5VDC") (class "Default")
      (node (ref "C1") (pin "2") (pinfunction "2_2") (pintype "passive"))
      (node (ref "C10") (pin "2") (pinfunction "2_2") (pintype "passive"))
      (node (ref "C11") (pin "2") (pinfunction "2_2") (pintype "passive"))
      (node (ref "C2") (pin "2") (pinfunction "2_2") (pintype "passive"))
      (node (ref "C8") (pin "1") (pinfunction "1_1") (pintype "passive"))
      (node (ref "C9") (pin "2") (pinfunction "2_2") (pintype "passive"))
      (node (ref "D2") (pin "1") (pinfunction "1_1") (pintype "passive"))
      (node (ref "L1") (pin "2") (pinfunction "2_2") (pintype "passive"))
      (node (ref "M1") (pin "1") (pinfunction "VCC_1") (pintype "passive"))
      (node (ref "U1") (pin "1") (pinfunction "VIN_1") (pintype "passive"))
      (node (ref "U2") (pin "4") (pinfunction "FB_4") (pintype "passive"))
    )
    (net (code "37") (name "12VDC") (class "Default")
      (node (ref "C5") (pin "2") (pinfunction "2_2") (pintype "passive"))
      (node (ref "C6") (pin "2") (pinfunction "2_2") (pintype "passive"))
      (node (ref "D3") (pin "1") (pinfunction "1_1") (pintype "passive"))
      (node (ref "D4") (pin "1") (pinfunction "1_1") (pintype "passive"))
      (node (ref "J10") (pin "1") (pinfunction "1_1") (pintype "passive"))
      (node (ref "J11") (pin "1") (pinfunction "1_1") (pintype "passive"))
      (node (ref "J4") (pin "1") (pinfunction "Vcc_1") (pintype "passive"))
      (node (ref "J7") (pin "1") (pinfunction "1_1") (pintype "passive"))
      (node (ref "RL1") (pin "5") (pinfunction "5_5") (pintype "passive"))
      (node (ref "RL2") (pin "1") (pinfunction "1_1") (pintype "passive"))
      (node (ref "RL2") (pin "5") (pinfunction "5_5") (pintype "passive"))
      (node (ref "U2") (pin "7") (pinfunction "VIN_7") (pintype "passive"))
    )
    (net (code "38") (name "GND") (class "Default")
      (node (ref "0") (pin "2") (pinfunction "GND_2") (pintype "passive"))
      (node (ref "0") (pin "4") (pinfunction "GND_4") (pintype "passive"))
      (node (ref "C1") (pin "1") (pinfunction "1_1") (pintype "passive"))
      (node (ref "C10") (pin "1") (pinfunction "1_1") (pintype "passive"))
      (node (ref "C11") (pin "1") (pinfunction "1_1") (pintype "passive"))
      (node (ref "C12") (pin "1") (pinfunction "1_1") (pintype "passive"))
      (node (ref "C13") (pin "1") (pinfunction "1_1") (pintype "passive"))
      (node (ref "C14") (pin "1") (pinfunction "1_1") (pintype "passive"))
      (node (ref "C15") (pin "1") (pinfunction "1_1") (pintype "passive"))
      (node (ref "C16") (pin "2") (pinfunction "2_2") (pintype "passive"))
      (node (ref "C17") (pin "1") (pinfunction "1_1") (pintype "passive"))
      (node (ref "C18") (pin "2") (pinfunction "2_2") (pintype "passive"))
      (node (ref "C19") (pin "2") (pinfunction "2_2") (pintype "passive"))
      (node (ref "C2") (pin "1") (pinfunction "1_1") (pintype "passive"))
      (node (ref "C20") (pin "2") (pinfunction "2_2") (pintype "passive"))
      (node (ref "C21") (pin "2") (pinfunction "2_2") (pintype "passive"))
      (node (ref "C3") (pin "1") (pinfunction "1_1") (pintype "passive"))
      (node (ref "C4") (pin "1") (pinfunction "1_1") (pintype "passive"))
      (node (ref "C5") (pin "1") (pinfunction "1_1") (pintype "passive"))
      (node (ref "C6") (pin "1") (pinfunction "1_1") (pintype "passive"))
      (node (ref "C8") (pin "2") (pinfunction "2_2") (pintype "passive"))
      (node (ref "C9") (pin "1") (pinfunction "1_1") (pintype "passive"))
      (node (ref "D1") (pin "1") (pinfunction "1_1") (pintype "passive"))
      (node (ref "J2") (pin "2") (pinfunction "2_2") (pintype "passive"))
      (node (ref "J3") (pin "3") (pinfunction "3_3") (pintype "passive"))
      (node (ref "J4") (pin "2") (pinfunction "GND_2") (pintype "passive"))
      (node (ref "J4") (pin "3") (pinfunction "SH_3") (pintype "passive"))
      (node (ref "J6") (pin "5") (pinfunction "GND_5") (pintype "passive"))
      (node (ref "J7") (pin "3") (pinfunction "3_3") (pintype "passive"))
      (node (ref "J8") (pin "5") (pinfunction "GND_5") (pintype "passive"))
      (node (ref "M1") (pin "2") (pinfunction "GND_2") (pintype "passive"))
      (node (ref "Q1") (pin "2") (pinfunction "E_2") (pintype "passive"))
      (node (ref "Q2") (pin "2") (pinfunction "E_2") (pintype "passive"))
      (node (ref "Q3") (pin "3") (pinfunction "D_3") (pintype "passive"))
      (node (ref "Q4") (pin "3") (pinfunction "D_3") (pintype "passive"))
      (node (ref "R12") (pin "1") (pinfunction "1_1") (pintype "passive"))
      (node (ref "R13") (pin "1") (pinfunction "1_1") (pintype "passive"))
      (node (ref "R6") (pin "1") (pinfunction "1_1") (pintype "passive"))
      (node (ref "R7") (pin "1") (pinfunction "1_1") (pintype "passive"))
      (node (ref "R9") (pin "1") (pinfunction "1_1") (pintype "passive"))
      (node (ref "U1") (pin "2") (pinfunction "GND_2") (pintype "passive"))
      (node (ref "U2") (pin "6") (pinfunction "GND_6") (pintype "passive"))
      (node (ref "U3") (pin "2") (pinfunction "GND_2") (pintype "power_in"))
      (node (ref "U4") (pin "10") (pinfunction "VSS_10") (pintype "passive"))
      (node (ref "U4") (pin "20") (pinfunction "VSSA_20") (pintype "passive"))
      (node (ref "U4") (pin "27") (pinfunction "VSS_27") (pintype "passive"))
      (node (ref "U4") (pin "74") (pinfunction "VSS_74") (pintype "passive"))
      (node (ref "U4") (pin "99") (pinfunction "VSS_99") (pintype "passive"))
    )
    (net (code "39") (name "Net-(0-Pad1)") (class "Default")
      (node (ref "0") (pin "1") (pinfunction "1_1") (pintype "passive"))
      (node (ref "C13") (pin "2") (pinfunction "2_2") (pintype "passive"))
      (node (ref "R8") (pin "1") (pinfunction "1_1") (pintype "passive"))
    )
    (net (code "40") (name "Net-(J8-Vcc)") (class "Default")
      (node (ref "D2") (pin "2") (pinfunction "2_2") (pintype "passive"))
      (node (ref "J8") (pin "1") (pinfunction "Vcc_1") (pintype "passive"))
    )
    (net (code "41") (name "Net-(Q1-B)") (class "Default")
      (node (ref "Q1") (pin "1") (pinfunction "B_1") (pintype "passive"))
      (node (ref "R3") (pin "2") (pinfunction "2_2") (pintype "passive"))
      (node (ref "R6") (pin "2") (pinfunction "2_2") (pintype "passive"))
    )
    (net (code "42") (name "Net-(Q1-C)") (class "Default")
      (node (ref "D3") (pin "2") (pinfunction "2_2") (pintype "passive"))
      (node (ref "Q1") (pin "3") (pinfunction "C_3") (pintype "passive"))
      (node (ref "RL1") (pin "4") (pinfunction "4_4") (pintype "passive"))
    )
    (net (code "43") (name "Net-(Q2-B)") (class "Default")
      (node (ref "Q2") (pin "1") (pinfunction "B_1") (pintype "passive"))
      (node (ref "R4") (pin "2") (pinfunction "2_2") (pintype "passive"))
      (node (ref "R7") (pin "2") (pinfunction "2_2") (pintype "passive"))
    )
    (net (code "44") (name "Net-(Q2-C)") (class "Default")
      (node (ref "D4") (pin "2") (pinfunction "2_2") (pintype "passive"))
      (node (ref "Q2") (pin "3") (pinfunction "C_3") (pintype "passive"))
      (node (ref "RL2") (pin "4") (pinfunction "4_4") (pintype "passive"))
    )
    (net (code "45") (name "Net-(Q3-G)") (class "Default")
      (node (ref "J10") (pin "2") (pinfunction "2_2") (pintype "passive"))
      (node (ref "Q3") (pin "2") (pinfunction "G_2") (pintype "passive"))
    )
    (net (code "46") (name "Net-(Q3-S)") (class "Default")
      (node (ref "Q3") (pin "1") (pinfunction "S_1") (pintype "passive"))
      (node (ref "R10") (pin "2") (pinfunction "2_2") (pintype "passive"))
      (node (ref "R12") (pin "2") (pinfunction "2_2") (pintype "passive"))
    )
    (net (code "47") (name "Net-(Q4-G)") (class "Default")
      (node (ref "J11") (pin "2") (pinfunction "2_2") (pintype "passive"))
      (node (ref "Q4") (pin "2") (pinfunction "G_2") (pintype "passive"))
    )
    (net (code "48") (name "Net-(Q4-S)") (class "Default")
      (node (ref "Q4") (pin "1") (pinfunction "S_1") (pintype "passive"))
      (node (ref "R11") (pin "2") (pinfunction "2_2") (pintype "passive"))
      (node (ref "R13") (pin "2") (pinfunction "2_2") (pintype "passive"))
    )
    (net (code "49") (name "Net-(U2-CB)") (class "Default")
      (node (ref "C7") (pin "1") (pinfunction "1_1") (pintype "passive"))
      (node (ref "U2") (pin "1") (pinfunction "CB_1") (pintype "passive"))
    )
    (net (code "50") (name "Net-(U2-VSW)") (class "Default")
      (node (ref "C7") (pin "2") (pinfunction "2_2") (pintype "passive"))
      (node (ref "D1") (pin "2") (pinfunction "2_2") (pintype "passive"))
      (node (ref "L1") (pin "1") (pinfunction "1_1") (pintype "passive"))
      (node (ref "U2") (pin "8") (pinfunction "VSW_8") (pintype "passive"))
    )
    (net (code "51") (name "unconnected-(J8-NC-Pad4)") (class "Default")
      (node (ref "J8") (pin "4") (pinfunction "NC_4") (pintype "passive+no_connect"))
    )
    (net (code "52") (name "unconnected-(RL2-Pad3)") (class "Default")
      (node (ref "RL2") (pin "3") (pinfunction "3_3") (pintype "passive"))
    )
    (net (code "53") (name "unconnected-(U2-EN-Pad5)") (class "Default")
      (node (ref "U2") (pin "5") (pinfunction "EN_5") (pintype "passive+no_connect"))
    )
    (net (code "54") (name "unconnected-(U2-NC-Pad2)") (class "Default")
      (node (ref "U2") (pin "2") (pinfunction "NC_2") (pintype "passive+no_connect"))
    )
    (net (code "55") (name "unconnected-(U2-NC-Pad3)") (class "Default")
      (node (ref "U2") (pin "3") (pinfunction "NC_3") (pintype "passive+no_connect"))
    )
    (net (code "56") (name "unconnected-(U4-PA0-Pad23)") (class "Default")
      (node (ref "U4") (pin "23") (pinfunction "PA0_23") (pintype "passive+no_connect"))
    )
    (net (code "57") (name "unconnected-(U4-PA1-Pad24)") (class "Default")
      (node (ref "U4") (pin "24") (pinfunction "PA1_24") (pintype "passive+no_connect"))
    )
    (net (code "58") (name "unconnected-(U4-PA2-Pad25)") (class "Default")
      (node (ref "U4") (pin "25") (pinfunction "PA2_25") (pintype "passive+no_connect"))
    )
    (net (code "59") (name "unconnected-(U4-PA3-Pad26)") (class "Default")
      (node (ref "U4") (pin "26") (pinfunction "PA3_26") (pintype "passive+no_connect"))
    )
    (net (code "60") (name "unconnected-(U4-PA4-Pad29)") (class "Default")
      (node (ref "U4") (pin "29") (pinfunction "PA4_29") (pintype "passive+no_connect"))
    )
    (net (code "61") (name "unconnected-(U4-PA5-Pad30)") (class "Default")
      (node (ref "U4") (pin "30") (pinfunction "PA5_30") (pintype "passive+no_connect"))
    )
    (net (code "62") (name "unconnected-(U4-PA6-Pad31)") (class "Default")
      (node (ref "U4") (pin "31") (pinfunction "PA6_31") (pintype "passive+no_connect"))
    )
    (net (code "63") (name "unconnected-(U4-PA7-Pad32)") (class "Default")
      (node (ref "U4") (pin "32") (pinfunction "PA7_32") (pintype "passive+no_connect"))
    )
    (net (code "64") (name "unconnected-(U4-PA8-Pad67)") (class "Default")
      (node (ref "U4") (pin "67") (pinfunction "PA8_67") (pintype "passive+no_connect"))
    )
    (net (code "65") (name "unconnected-(U4-PA9-Pad68)") (class "Default")
      (node (ref "U4") (pin "68") (pinfunction "PA9_68") (pintype "passive+no_connect"))
    )
    (net (code "66") (name "unconnected-(U4-PA10-Pad69)") (class "Default")
      (node (ref "U4") (pin "69") (pinfunction "PA10_69") (pintype "passive+no_connect"))
    )
    (net (code "67") (name "unconnected-(U4-PB0-Pad35)") (class "Default")
      (node (ref "U4") (pin "35") (pinfunction "PB0_35") (pintype "passive+no_connect"))
    )
    (net (code "68") (name "unconnected-(U4-PB1-Pad36)") (class "Default")
      (node (ref "U4") (pin "36") (pinfunction "PB1_36") (pintype "passive+no_connect"))
    )
    (net (code "69") (name "unconnected-(U4-PB2-Pad37)") (class "Default")
      (node (ref "U4") (pin "37") (pinfunction "PB2_37") (pintype "passive+no_connect"))
    )
    (net (code "70") (name "unconnected-(U4-PB4-Pad90)") (class "Default")
      (node (ref "U4") (pin "90") (pinfunction "PB4_90") (pintype "passive+no_connect"))
    )
    (net (code "71") (name "unconnected-(U4-PB5-Pad91)") (class "Default")
      (node (ref "U4") (pin "91") (pinfunction "PB5_91") (pintype "passive"))
    )
    (net (code "72") (name "unconnected-(U4-PB8-Pad95)") (class "Default")
      (node (ref "U4") (pin "95") (pinfunction "PB8_95") (pintype "passive+no_connect"))
    )
    (net (code "73") (name "unconnected-(U4-PB9-Pad96)") (class "Default")
      (node (ref "U4") (pin "96") (pinfunction "PB9_96") (pintype "passive+no_connect"))
    )
    (net (code "74") (name "unconnected-(U4-PB10-Pad47)") (class "Default")
      (node (ref "U4") (pin "47") (pinfunction "PB10_47") (pintype "passive+no_connect"))
    )
    (net (code "75") (name "unconnected-(U4-PB11-Pad48)") (class "Default")
      (node (ref "U4") (pin "48") (pinfunction "PB11_48") (pintype "passive+no_connect"))
    )
    (net (code "76") (name "unconnected-(U4-PB12-Pad51)") (class "Default")
      (node (ref "U4") (pin "51") (pinfunction "PB12_51") (pintype "passive+no_connect"))
    )
    (net (code "77") (name "unconnected-(U4-PB13-Pad52)") (class "Default")
      (node (ref "U4") (pin "52") (pinfunction "PB13_52") (pintype "passive+no_connect"))
    )
    (net (code "78") (name "unconnected-(U4-PB14-Pad53)") (class "Default")
      (node (ref "U4") (pin "53") (pinfunction "PB14_53") (pintype "passive+no_connect"))
    )
    (net (code "79") (name "unconnected-(U4-PC0-Pad15)") (class "Default")
      (node (ref "U4") (pin "15") (pinfunction "PC0_15") (pintype "passive"))
    )
    (net (code "80") (name "unconnected-(U4-PC2-Pad17)") (class "Default")
      (node (ref "U4") (pin "17") (pinfunction "PC2_17") (pintype "passive+no_connect"))
    )
    (net (code "81") (name "unconnected-(U4-PC3-Pad18)") (class "Default")
      (node (ref "U4") (pin "18") (pinfunction "PC3_18") (pintype "passive+no_connect"))
    )
    (net (code "82") (name "unconnected-(U4-PC4-Pad33)") (class "Default")
      (node (ref "U4") (pin "33") (pinfunction "PC4_33") (pintype "passive+no_connect"))
    )
    (net (code "83") (name "unconnected-(U4-PC5-Pad34)") (class "Default")
      (node (ref "U4") (pin "34") (pinfunction "PC5_34") (pintype "passive+no_connect"))
    )
    (net (code "84") (name "unconnected-(U4-PC8-Pad65)") (class "Default")
      (node (ref "U4") (pin "65") (pinfunction "PC8_65") (pintype "passive+no_connect"))
    )
    (net (code "85") (name "unconnected-(U4-PC9-Pad66)") (class "Default")
      (node (ref "U4") (pin "66") (pinfunction "PC9_66") (pintype "passive+no_connect"))
    )
    (net (code "86") (name "unconnected-(U4-PC10-Pad78)") (class "Default")
      (node (ref "U4") (pin "78") (pinfunction "PC10_78") (pintype "passive"))
    )
    (net (code "87") (name "unconnected-(U4-PC13-Pad7)") (class "Default")
      (node (ref "U4") (pin "7") (pinfunction "PC13_7") (pintype "passive+no_connect"))
    )
    (net (code "88") (name "unconnected-(U4-PC14-Pad8)") (class "Default")
      (node (ref "U4") (pin "8") (pinfunction "PC14_8") (pintype "passive+no_connect"))
    )
    (net (code "89") (name "unconnected-(U4-PC15-Pad9)") (class "Default")
      (node (ref "U4") (pin "9") (pinfunction "PC15_9") (pintype "passive+no_connect"))
    )
    (net (code "90") (name "unconnected-(U4-PD1-Pad82)") (class "Default")
      (node (ref "U4") (pin "82") (pinfunction "PD1_82") (pintype "passive+no_connect"))
    )
    (net (code "91") (name "unconnected-(U4-PD3-Pad84)") (class "Default")
      (node (ref "U4") (pin "84") (pinfunction "PD3_84") (pintype "passive+no_connect"))
    )
    (net (code "92") (name "unconnected-(U4-PD4-Pad85)") (class "Default")
      (node (ref "U4") (pin "85") (pinfunction "PD4_85") (pintype "passive+no_connect"))
    )
    (net (code "93") (name "unconnected-(U4-PD5-Pad86)") (class "Default")
      (node (ref "U4") (pin "86") (pinfunction "PD5_86") (pintype "passive+no_connect"))
    )
    (net (code "94") (name "unconnected-(U4-PD6-Pad87)") (class "Default")
      (node (ref "U4") (pin "87") (pinfunction "PD6_87") (pintype "passive+no_connect"))
    )
    (net (code "95") (name "unconnected-(U4-PD7-Pad88)") (class "Default")
      (node (ref "U4") (pin "88") (pinfunction "PD7_88") (pintype "passive+no_connect"))
    )
    (net (code "96") (name "unconnected-(U4-PD8-Pad55)") (class "Default")
      (node (ref "U4") (pin "55") (pinfunction "PD8_55") (pintype "passive+no_connect"))
    )
    (net (code "97") (name "unconnected-(U4-PD9-Pad56)") (class "Default")
      (node (ref "U4") (pin "56") (pinfunction "PD9_56") (pintype "passive+no_connect"))
    )
    (net (code "98") (name "unconnected-(U4-PD10-Pad57)") (class "Default")
      (node (ref "U4") (pin "57") (pinfunction "PD10_57") (pintype "passive"))
    )
    (net (code "99") (name "unconnected-(U4-PD11-Pad58)") (class "Default")
      (node (ref "U4") (pin "58") (pinfunction "PD11_58") (pintype "passive+no_connect"))
    )
    (net (code "100") (name "unconnected-(U4-PD12-Pad59)") (class "Default")
      (node (ref "U4") (pin "59") (pinfunction "PD12_59") (pintype "passive+no_connect"))
    )
    (net (code "101") (name "unconnected-(U4-PD13-Pad60)") (class "Default")
      (node (ref "U4") (pin "60") (pinfunction "PD13_60") (pintype "passive+no_connect"))
    )
    (net (code "102") (name "unconnected-(U4-PE0-Pad97)") (class "Default")
      (node (ref "U4") (pin "97") (pinfunction "PE0_97") (pintype "passive+no_connect"))
    )
    (net (code "103") (name "unconnected-(U4-PE1-Pad98)") (class "Default")
      (node (ref "U4") (pin "98") (pinfunction "PE1_98") (pintype "passive"))
    )
    (net (code "104") (name "unconnected-(U4-PE2-Pad1)") (class "Default")
      (node (ref "U4") (pin "1") (pinfunction "PE2_1") (pintype "passive"))
    )
    (net (code "105") (name "unconnected-(U4-PE3-Pad2)") (class "Default")
      (node (ref "U4") (pin "2") (pinfunction "PE3_2") (pintype "passive+no_connect"))
    )
    (net (code "106") (name "unconnected-(U4-PE4-Pad3)") (class "Default")
      (node (ref "U4") (pin "3") (pinfunction "PE4_3") (pintype "passive"))
    )
    (net (code "107") (name "unconnected-(U4-PE5-Pad4)") (class "Default")
      (node (ref "U4") (pin "4") (pinfunction "PE5_4") (pintype "passive+no_connect"))
    )
    (net (code "108") (name "unconnected-(U4-PE6-Pad5)") (class "Default")
      (node (ref "U4") (pin "5") (pinfunction "PE6_5") (pintype "passive+no_connect"))
    )
    (net (code "109") (name "unconnected-(U4-PE7-Pad38)") (class "Default")
      (node (ref "U4") (pin "38") (pinfunction "PE7_38") (pintype "passive+no_connect"))
    )
    (net (code "110") (name "unconnected-(U4-PE8-Pad39)") (class "Default")
      (node (ref "U4") (pin "39") (pinfunction "PE8_39") (pintype "passive+no_connect"))
    )
    (net (code "111") (name "unconnected-(U4-PE9-Pad40)") (class "Default")
      (node (ref "U4") (pin "40") (pinfunction "PE9_40") (pintype "passive"))
    )
    (net (code "112") (name "unconnected-(U4-PE10-Pad41)") (class "Default")
      (node (ref "U4") (pin "41") (pinfunction "PE10_41") (pintype "passive"))
    )
    (net (code "113") (name "unconnected-(U4-PE11-Pad42)") (class "Default")
      (node (ref "U4") (pin "42") (pinfunction "PE11_42") (pintype "passive+no_connect"))
    )
    (net (code "114") (name "unconnected-(U4-PE12-Pad43)") (class "Default")
      (node (ref "U4") (pin "43") (pinfunction "PE12_43") (pintype "passive+no_connect"))
    )
    (net (code "115") (name "unconnected-(U4-PE13-Pad44)") (class "Default")
      (node (ref "U4") (pin "44") (pinfunction "PE13_44") (pintype "passive+no_connect"))
    )
    (net (code "116") (name "unconnected-(U4-PE14-Pad45)") (class "Default")
      (node (ref "U4") (pin "45") (pinfunction "PE14_45") (pintype "passive+no_connect"))
    )
    (net (code "117") (name "unconnected-(U4-PE15-Pad46)") (class "Default")
      (node (ref "U4") (pin "46") (pinfunction "PE15_46") (pintype "passive+no_connect"))
    )
  )
)
